# MotorDriver-rev1.net
KiCad netlist of a schematic drawn in EAGLE
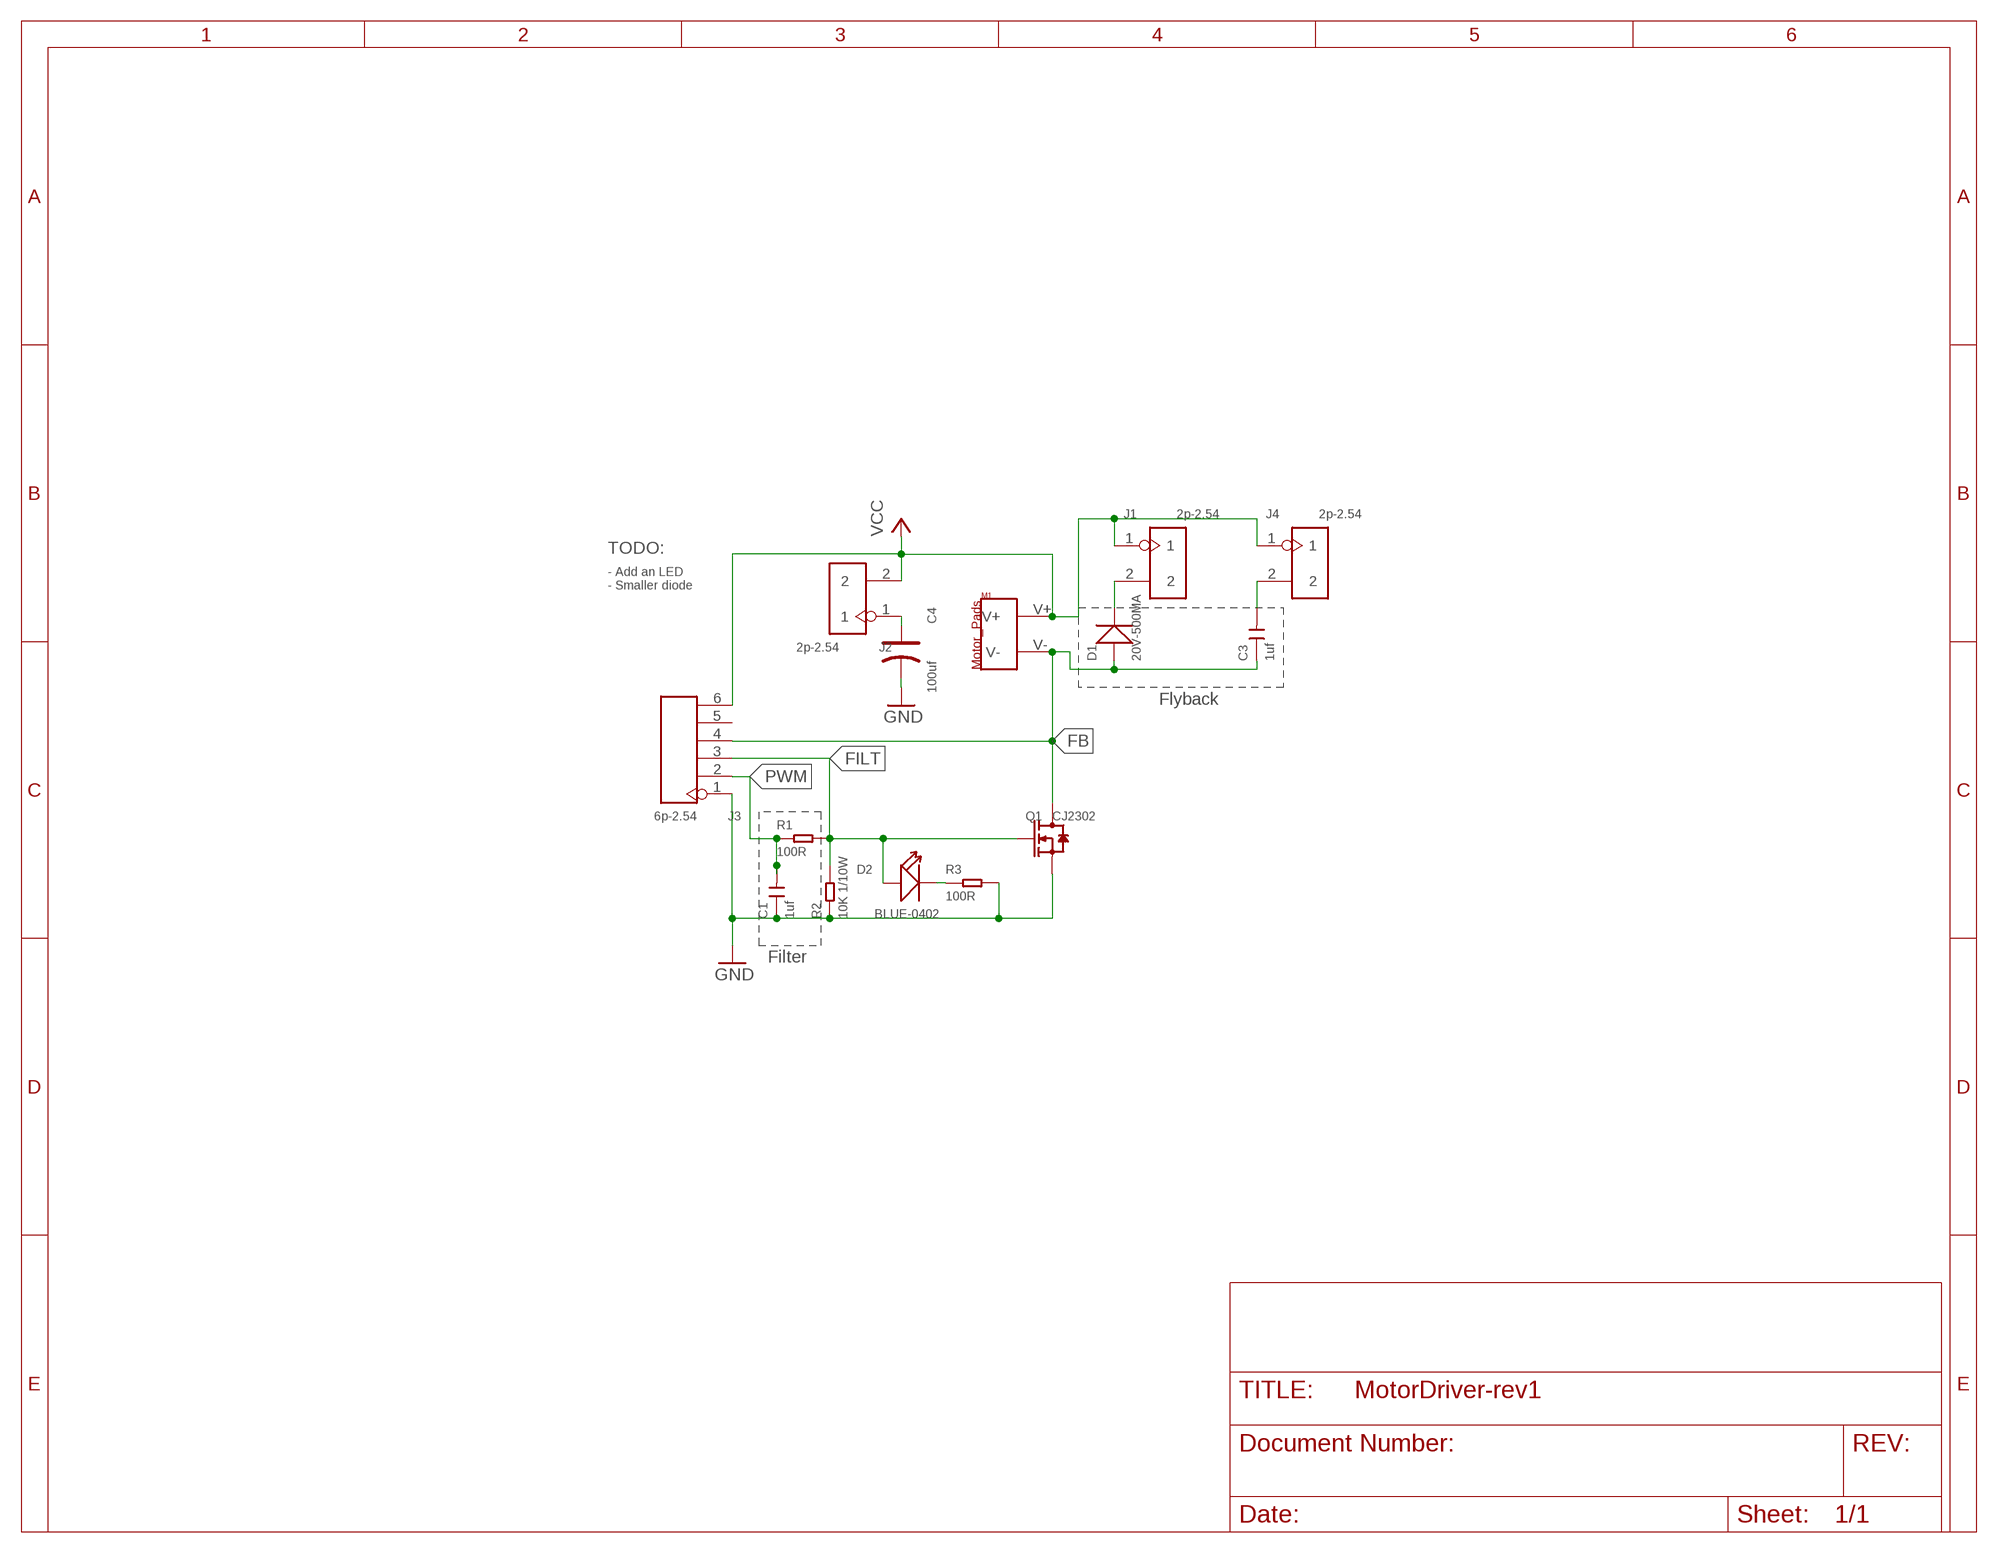
[diagram p0: schematic, sheet 1]

(export (version "E")
  (design (tool "Eeschema 10.0.6"))
  (components
    (comp (ref "C1")
      (value "1uf")
      (footprint "eagle-import:C0402")
      (fields (field (name "MPN") "CC0402KRX5R6BB105"))
      (libsource (lib "eagle-import") (part "CERAMIC-1UF-10V-10%-X5R(0402)"))
    )
    (comp (ref "C3")
      (value "1uf")
      (footprint "eagle-import:C0603")
      (fields (field (name "MPN") "CC0603KRX7R8BB105"))
      (libsource (lib "eagle-import") (part "CERAMIC-1UF-25V-10%-X7R(0603)"))
    )
    (comp (ref "C4")
      (value "100uf")
      (footprint "eagle-import:AVX-B")
      (fields (field (name "MPN") "TAJB107M010#NJ"))
      (libsource (lib "eagle-import") (part "TANTALUM-SMD-100UF-10V(AVX-B)"))
    )
    (comp (ref "D1")
      (value "20V-500MA")
      (footprint "eagle-import:SOD-123")
      (fields (field (name "MPN") "SS0520-7-F"))
      (libsource (lib "eagle-import") (part "SMD-DIODE-SCHOTTKY-20V-500MA(SOD-123)"))
    )
    (comp (ref "D2")
      (value "BLUE-0402")
      (footprint "eagle-import:LED-0402")
      (fields (field (name "MPN") "BL-HB337A-AV-TRB"))
      (libsource (lib "eagle-import") (part "SMD-LED-CLEAR-BLUE(0402)"))
    )
    (comp (ref "J1")
      (value "2p-2.54")
      (footprint "eagle-import:H2-2.54")
      (fields (field (name "MPN") "P125-1102A0BS116A1"))
      (libsource (lib "eagle-import") (part "DIP-BLACK-MALE-HEADER-VERT(2P-2.54)"))
    )
    (comp (ref "J2")
      (value "2p-2.54")
      (footprint "eagle-import:H2-2.54")
      (fields (field (name "MPN") "P125-1102A0BS116A1"))
      (libsource (lib "eagle-import") (part "DIP-BLACK-MALE-HEADER-VERT(2P-2.54)"))
    )
    (comp (ref "J3")
      (value "6p-2.54")
      (footprint "eagle-import:H6-2.54")
      (fields (field (name "MPN") "P125-1106A1BS116A1"))
      (libsource (lib "eagle-import") (part "DIP-BLACK-MALE-HEADER(6P-2.54)"))
    )
    (comp (ref "J4")
      (value "2p-2.54")
      (footprint "eagle-import:H2-2.54")
      (fields (field (name "MPN") "P125-1102A0BS116A1"))
      (libsource (lib "eagle-import") (part "DIP-BLACK-MALE-HEADER-VERT(2P-2.54)"))
    )
    (comp (ref "M1")
      (value "MOTOR_PADS")
      (footprint "eagle-import:MOTOR_PADS")
      (libsource (lib "eagle-import") (part "MOTOR_PADS"))
    )
    (comp (ref "Q1")
      (value "CJ2302")
      (footprint "eagle-import:SOT-23")
      (libsource (lib "eagle-import") (part "SMD-MOSFET-N-CH-20V-2.1A-CJ2302(SOT-23)"))
    )
    (comp (ref "R1")
      (value "100R")
      (footprint "eagle-import:R0603")
      (fields (field (name "MPN") "RC0603JR-07100RL"))
      (libsource (lib "eagle-import") (part "SMD-RES-100R-5%-1/10W(0603)"))
    )
    (comp (ref "R2")
      (value "10K 1/10W")
      (footprint "eagle-import:R0603")
      (fields (field (name "MPN") "RC0603JR-0710KL"))
      (libsource (lib "eagle-import") (part "SMD-RES-10K-5%-1/10W(0603)"))
    )
    (comp (ref "R3")
      (value "100R")
      (footprint "eagle-import:R0402")
      (fields (field (name "MPN") "RC0402JR-07100RL"))
      (libsource (lib "eagle-import") (part "SMD-RES-100R-5%-1/16W(0402)"))
    )
  )
  (nets
    (net (code "1") (name "FB") (class "Default")
      (node (ref "C3") (pin "1") (pinfunction "1_1") (pintype "passive"))
      (node (ref "D1") (pin "+") (pinfunction "+_+") (pintype "passive"))
      (node (ref "J3") (pin "4") (pinfunction "4_4") (pintype "bidirectional"))
      (node (ref "M1") (pin "V-") (pinfunction "V-_V-") (pintype "bidirectional"))
      (node (ref "Q1") (pin "3") (pinfunction "D_3") (pintype "passive"))
    )
    (net (code "2") (name "FILT") (class "Default")
      (node (ref "D2") (pin "+") (pinfunction "+_+") (pintype "passive"))
      (node (ref "J3") (pin "3") (pinfunction "3_3") (pintype "bidirectional"))
      (node (ref "Q1") (pin "1") (pinfunction "G_1") (pintype "passive"))
      (node (ref "R1") (pin "2") (pinfunction "2_2") (pintype "passive"))
      (node (ref "R2") (pin "2") (pinfunction "2_2") (pintype "passive"))
    )
    (net (code "3") (name "GND") (class "Default")
      (node (ref "C1") (pin "1") (pinfunction "1_1") (pintype "passive"))
      (node (ref "C4") (pin "-") (pinfunction "-_-") (pintype "passive"))
      (node (ref "J3") (pin "1") (pinfunction "1_1") (pintype "bidirectional"))
      (node (ref "Q1") (pin "2") (pinfunction "S_2") (pintype "passive"))
      (node (ref "R2") (pin "1") (pinfunction "1_1") (pintype "passive"))
      (node (ref "R3") (pin "2") (pinfunction "2_2") (pintype "passive"))
    )
    (net (code "4") (name "Net-(C3-Pad2)") (class "Default")
      (node (ref "C3") (pin "2") (pinfunction "2_2") (pintype "passive"))
      (node (ref "J4") (pin "2") (pinfunction "2_2") (pintype "bidirectional"))
    )
    (net (code "5") (name "Net-(C4-Pad+)") (class "Default")
      (node (ref "C4") (pin "+") (pinfunction "+_+") (pintype "passive"))
      (node (ref "J2") (pin "1") (pinfunction "1_1") (pintype "bidirectional"))
    )
    (net (code "6") (name "Net-(D1-Pad-)") (class "Default")
      (node (ref "D1") (pin "-") (pinfunction "-_-") (pintype "passive"))
      (node (ref "J1") (pin "2") (pinfunction "2_2") (pintype "bidirectional"))
    )
    (net (code "7") (name "Net-(D2-Pad-)") (class "Default")
      (node (ref "D2") (pin "-") (pinfunction "-_-") (pintype "passive"))
      (node (ref "R3") (pin "1") (pinfunction "1_1") (pintype "passive"))
    )
    (net (code "8") (name "PWM") (class "Default")
      (node (ref "C1") (pin "2") (pinfunction "2_2") (pintype "passive"))
      (node (ref "J3") (pin "2") (pinfunction "2_2") (pintype "bidirectional"))
      (node (ref "R1") (pin "1") (pinfunction "1_1") (pintype "passive"))
    )
    (net (code "9") (name "VCC") (class "Default")
      (node (ref "J1") (pin "1") (pinfunction "1_1") (pintype "bidirectional"))
      (node (ref "J2") (pin "2") (pinfunction "2_2") (pintype "bidirectional"))
      (node (ref "J3") (pin "6") (pinfunction "6_6") (pintype "bidirectional"))
      (node (ref "J4") (pin "1") (pinfunction "1_1") (pintype "bidirectional"))
      (node (ref "M1") (pin "V+") (pinfunction "V+_V+") (pintype "bidirectional"))
    )
    (net (code "10") (name "unconnected-(J3-Pad5)") (class "Default")
      (node (ref "J3") (pin "5") (pinfunction "5_5") (pintype "bidirectional"))
    )
  )
)
